# mainboard.net
KiCad netlist of a schematic drawn in EAGLE
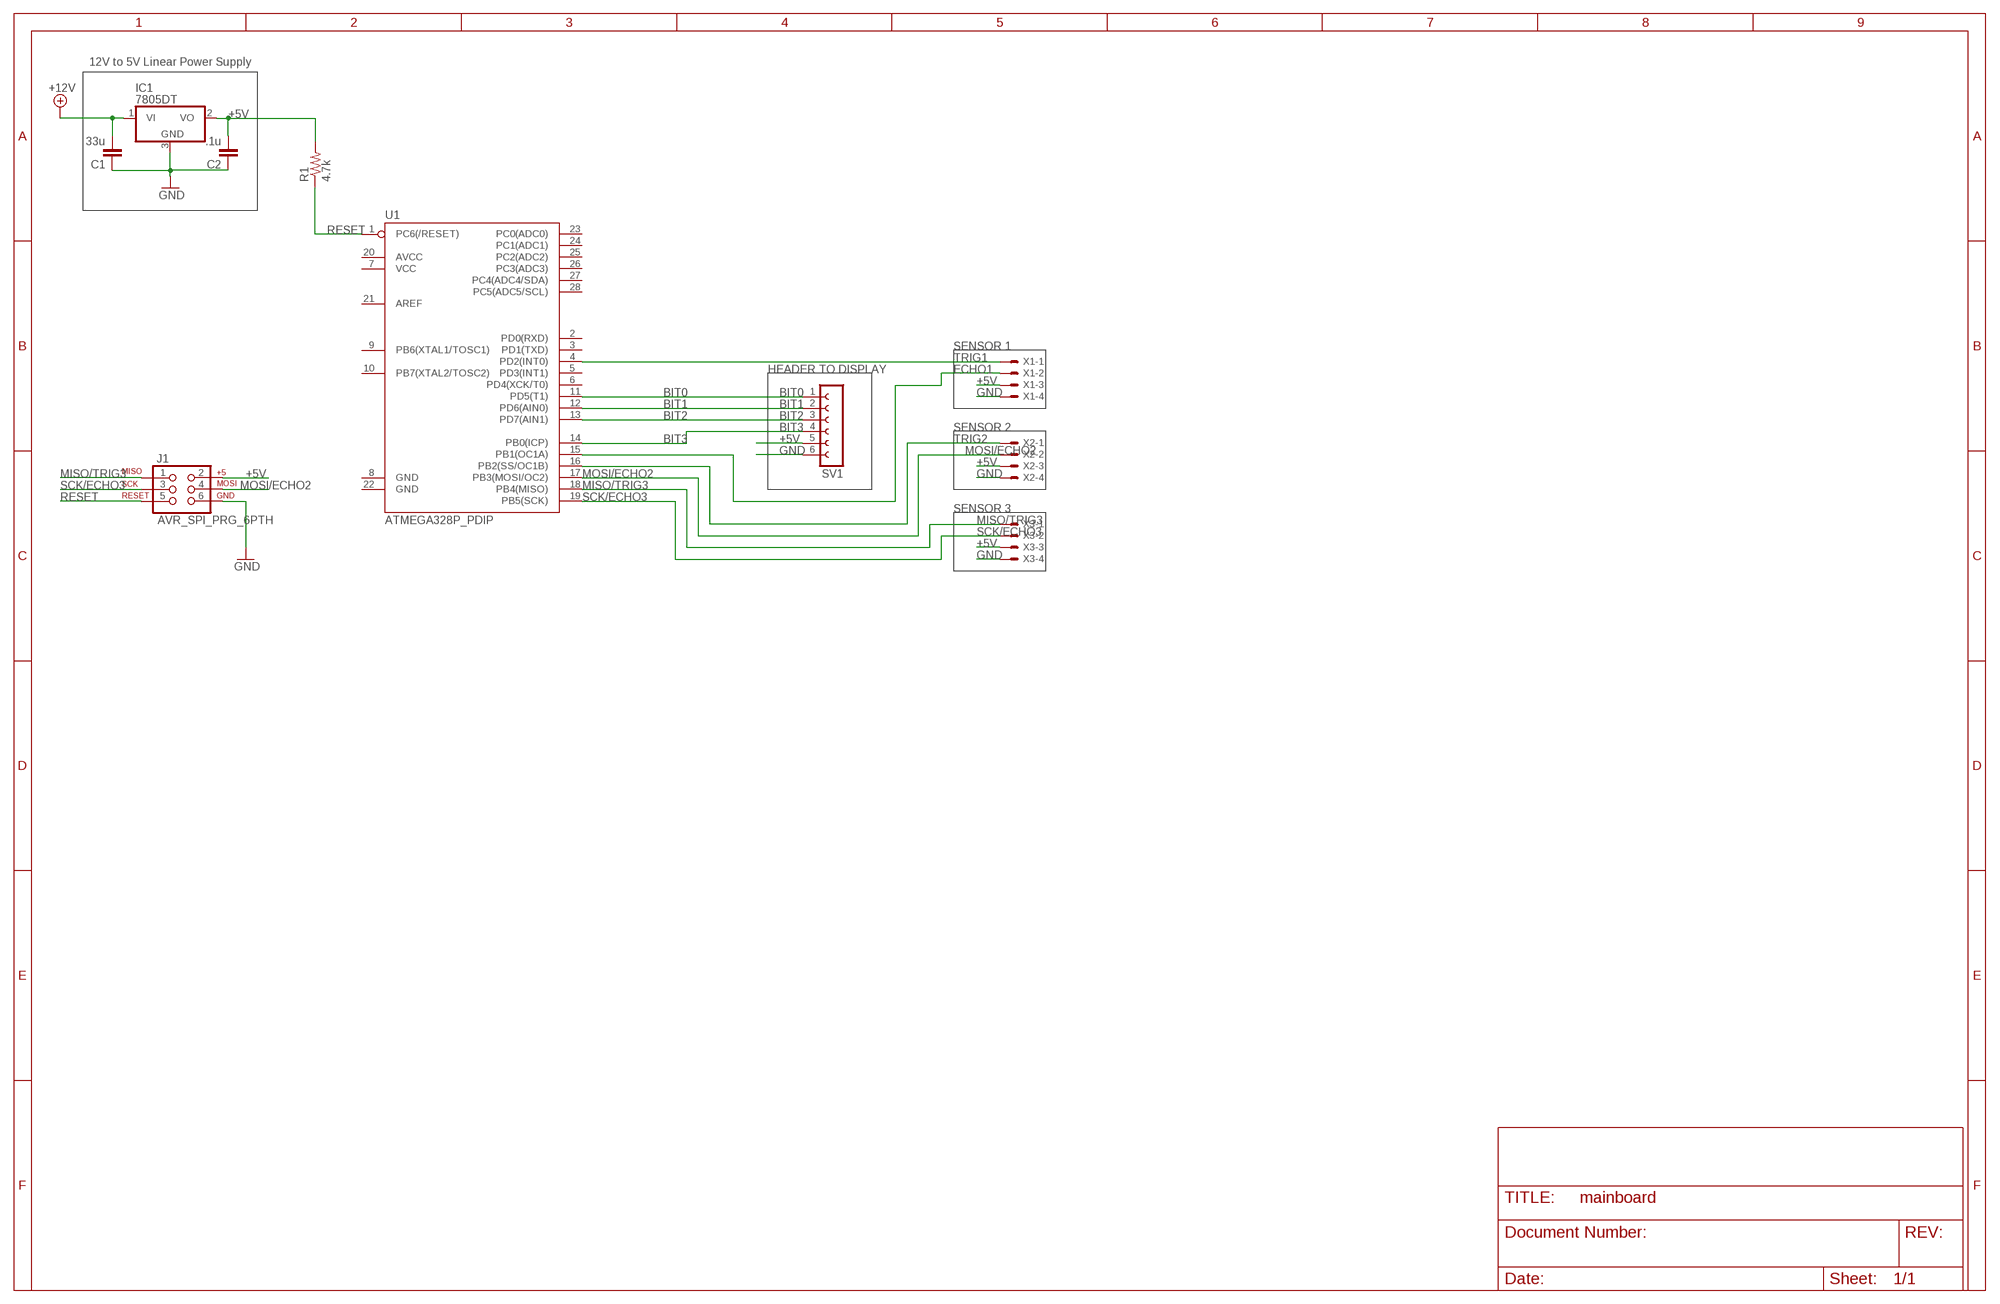
[diagram p0: schematic, sheet 1]

(export (version "E")
  (design (tool "Eeschema 10.0.6"))
  (components
    (comp (ref "C1")
      (value "33u")
      (footprint "eagle-import:C025-024X044")
      (libsource (lib "eagle-import") (part "C-EU025-024X044"))
    )
    (comp (ref "C2")
      (value ".1u")
      (footprint "eagle-import:C025-024X044")
      (libsource (lib "eagle-import") (part "C-EU025-024X044"))
    )
    (comp (ref "IC1")
      (value "7805DT")
      (footprint "eagle-import:TO252")
      (libsource (lib "eagle-import") (part "78DT05"))
    )
    (comp (ref "J1")
      (value "AVR_SPI_PRG_6PTH")
      (footprint "eagle-import:2X3")
      (libsource (lib "eagle-import") (part "AVR_SPI_PRG_6PTH"))
    )
    (comp (ref "R1")
      (value "4.7k")
      (footprint "eagle-import:0414V")
      (libsource (lib "eagle-import") (part "R-US_0414/5V"))
    )
    (comp (ref "SV1")
      (value "FE06-1")
      (footprint "eagle-import:FE06")
      (libsource (lib "eagle-import") (part "FE06-1"))
    )
    (comp (ref "U1")
      (value "ATMEGA328P_PDIP")
      (footprint "eagle-import:DIL28-3")
      (libsource (lib "eagle-import") (part "ATMEGA328P_PDIP"))
    )
    (comp (ref "X1")
      (value "KK-156-4")
      (footprint "eagle-import:KK-156-4")
      (libsource (lib "eagle-import") (part "KK-156-4"))
    )
    (comp (ref "X2")
      (value "KK-156-4")
      (footprint "eagle-import:KK-156-4")
      (libsource (lib "eagle-import") (part "KK-156-4"))
    )
    (comp (ref "X3")
      (value "KK-156-4")
      (footprint "eagle-import:KK-156-4")
      (libsource (lib "eagle-import") (part "KK-156-4"))
    )
  )
  (nets
    (net (code "1") (name "+12V") (class "Default")
      (node (ref "C1") (pin "2") (pinfunction "2_2") (pintype "passive"))
      (node (ref "IC1") (pin "1") (pinfunction "VI_1") (pintype "input"))
    )
    (net (code "2") (name "/+5V") (class "Default")
      (node (ref "C2") (pin "2") (pinfunction "2_2") (pintype "passive"))
      (node (ref "IC1") (pin "2") (pinfunction "VO_2") (pintype "passive"))
      (node (ref "J1") (pin "2") (pinfunction "2_2") (pintype "passive"))
      (node (ref "R1") (pin "2") (pinfunction "2_2") (pintype "passive"))
      (node (ref "SV1") (pin "5") (pinfunction "5_5") (pintype "passive"))
      (node (ref "X1") (pin "3") (pinfunction "S_3") (pintype "passive"))
      (node (ref "X2") (pin "3") (pinfunction "S_3") (pintype "passive"))
      (node (ref "X3") (pin "3") (pinfunction "S_3") (pintype "passive"))
    )
    (net (code "3") (name "/BIT0") (class "Default")
      (node (ref "SV1") (pin "1") (pinfunction "1_1") (pintype "passive"))
      (node (ref "U1") (pin "11") (pinfunction "PD5(T1)_11") (pintype "bidirectional"))
    )
    (net (code "4") (name "/BIT1") (class "Default")
      (node (ref "SV1") (pin "2") (pinfunction "2_2") (pintype "passive"))
      (node (ref "U1") (pin "12") (pinfunction "PD6(AIN0)_12") (pintype "bidirectional"))
    )
    (net (code "5") (name "/BIT2") (class "Default")
      (node (ref "SV1") (pin "3") (pinfunction "3_3") (pintype "passive"))
      (node (ref "U1") (pin "13") (pinfunction "PD7(AIN1)_13") (pintype "bidirectional"))
    )
    (net (code "6") (name "/BIT3") (class "Default")
      (node (ref "SV1") (pin "4") (pinfunction "4_4") (pintype "passive"))
      (node (ref "U1") (pin "14") (pinfunction "PB0(ICP)_14") (pintype "bidirectional"))
    )
    (net (code "7") (name "/ECHO1") (class "Default")
      (node (ref "U1") (pin "15") (pinfunction "PB1(OC1A)_15") (pintype "bidirectional"))
      (node (ref "X1") (pin "2") (pinfunction "S_2") (pintype "passive"))
    )
    (net (code "8") (name "/MISO{slash}TRIG3") (class "Default")
      (node (ref "J1") (pin "1") (pinfunction "1_1") (pintype "passive"))
      (node (ref "U1") (pin "18") (pinfunction "PB4(MISO)_18") (pintype "bidirectional"))
      (node (ref "X3") (pin "1") (pinfunction "S_1") (pintype "passive"))
    )
    (net (code "9") (name "/MOSI{slash}ECHO2") (class "Default")
      (node (ref "J1") (pin "4") (pinfunction "4_4") (pintype "passive"))
      (node (ref "U1") (pin "17") (pinfunction "PB3(MOSI/OC2)_17") (pintype "bidirectional"))
      (node (ref "X2") (pin "2") (pinfunction "S_2") (pintype "passive"))
    )
    (net (code "10") (name "/RESET") (class "Default")
      (node (ref "J1") (pin "5") (pinfunction "5_5") (pintype "passive"))
      (node (ref "R1") (pin "1") (pinfunction "1_1") (pintype "passive"))
      (node (ref "U1") (pin "1") (pinfunction "PC6(/RESET)_1") (pintype "bidirectional"))
    )
    (net (code "11") (name "/SCK{slash}ECHO3") (class "Default")
      (node (ref "J1") (pin "3") (pinfunction "3_3") (pintype "passive"))
      (node (ref "U1") (pin "19") (pinfunction "PB5(SCK)_19") (pintype "bidirectional"))
      (node (ref "X3") (pin "2") (pinfunction "S_2") (pintype "passive"))
    )
    (net (code "12") (name "/TRIG1") (class "Default")
      (node (ref "U1") (pin "4") (pinfunction "PD2(INT0)_4") (pintype "bidirectional"))
      (node (ref "X1") (pin "1") (pinfunction "S_1") (pintype "passive"))
    )
    (net (code "13") (name "/TRIG2") (class "Default")
      (node (ref "U1") (pin "16") (pinfunction "PB2(SS/OC1B)_16") (pintype "bidirectional"))
      (node (ref "X2") (pin "1") (pinfunction "S_1") (pintype "passive"))
    )
    (net (code "14") (name "GND") (class "Default")
      (node (ref "C1") (pin "1") (pinfunction "1_1") (pintype "passive"))
      (node (ref "C2") (pin "1") (pinfunction "1_1") (pintype "passive"))
      (node (ref "IC1") (pin "3") (pinfunction "GND_3") (pintype "passive"))
      (node (ref "J1") (pin "6") (pinfunction "6_6") (pintype "passive"))
      (node (ref "SV1") (pin "6") (pinfunction "6_6") (pintype "passive"))
      (node (ref "X1") (pin "4") (pinfunction "S_4") (pintype "passive"))
      (node (ref "X2") (pin "4") (pinfunction "S_4") (pintype "passive"))
      (node (ref "X3") (pin "4") (pinfunction "S_4") (pintype "passive"))
    )
    (net (code "15") (name "unconnected-(U1-AREF-Pad21)") (class "Default")
      (node (ref "U1") (pin "21") (pinfunction "AREF_21") (pintype "bidirectional"))
    )
    (net (code "16") (name "unconnected-(U1-AVCC-Pad20)") (class "Default")
      (node (ref "U1") (pin "20") (pinfunction "AVCC_20") (pintype "bidirectional"))
    )
    (net (code "17") (name "unconnected-(U1-GND-Pad8)") (class "Default")
      (node (ref "U1") (pin "8") (pinfunction "GND_8") (pintype "bidirectional"))
    )
    (net (code "18") (name "unconnected-(U1-GND-Pad22)") (class "Default")
      (node (ref "U1") (pin "22") (pinfunction "GND_22") (pintype "bidirectional"))
    )
    (net (code "19") (name "unconnected-(U1-PB6(XTAL1{slash}TOSC1)-Pad9)") (class "Default")
      (node (ref "U1") (pin "9") (pinfunction "PB6(XTAL1/TOSC1)_9") (pintype "bidirectional"))
    )
    (net (code "20") (name "unconnected-(U1-PB7(XTAL2{slash}TOSC2)-Pad10)") (class "Default")
      (node (ref "U1") (pin "10") (pinfunction "PB7(XTAL2/TOSC2)_10") (pintype "bidirectional"))
    )
    (net (code "21") (name "unconnected-(U1-PC0(ADC0)-Pad23)") (class "Default")
      (node (ref "U1") (pin "23") (pinfunction "PC0(ADC0)_23") (pintype "bidirectional"))
    )
    (net (code "22") (name "unconnected-(U1-PC1(ADC1)-Pad24)") (class "Default")
      (node (ref "U1") (pin "24") (pinfunction "PC1(ADC1)_24") (pintype "bidirectional"))
    )
    (net (code "23") (name "unconnected-(U1-PC2(ADC2)-Pad25)") (class "Default")
      (node (ref "U1") (pin "25") (pinfunction "PC2(ADC2)_25") (pintype "bidirectional"))
    )
    (net (code "24") (name "unconnected-(U1-PC3(ADC3)-Pad26)") (class "Default")
      (node (ref "U1") (pin "26") (pinfunction "PC3(ADC3)_26") (pintype "bidirectional"))
    )
    (net (code "25") (name "unconnected-(U1-PC4(ADC4{slash}SDA)-Pad27)") (class "Default")
      (node (ref "U1") (pin "27") (pinfunction "PC4(ADC4/SDA)_27") (pintype "bidirectional"))
    )
    (net (code "26") (name "unconnected-(U1-PC5(ADC5{slash}SCL)-Pad28)") (class "Default")
      (node (ref "U1") (pin "28") (pinfunction "PC5(ADC5/SCL)_28") (pintype "bidirectional"))
    )
    (net (code "27") (name "unconnected-(U1-PD0(RXD)-Pad2)") (class "Default")
      (node (ref "U1") (pin "2") (pinfunction "PD0(RXD)_2") (pintype "bidirectional"))
    )
    (net (code "28") (name "unconnected-(U1-PD1(TXD)-Pad3)") (class "Default")
      (node (ref "U1") (pin "3") (pinfunction "PD1(TXD)_3") (pintype "bidirectional"))
    )
    (net (code "29") (name "unconnected-(U1-PD3(INT1)-Pad5)") (class "Default")
      (node (ref "U1") (pin "5") (pinfunction "PD3(INT1)_5") (pintype "bidirectional"))
    )
    (net (code "30") (name "unconnected-(U1-PD4(XCK{slash}T0)-Pad6)") (class "Default")
      (node (ref "U1") (pin "6") (pinfunction "PD4(XCK/T0)_6") (pintype "bidirectional"))
    )
    (net (code "31") (name "unconnected-(U1-VCC-Pad7)") (class "Default")
      (node (ref "U1") (pin "7") (pinfunction "VCC_7") (pintype "bidirectional"))
    )
  )
)
